# 1-Schematic_ESP-BOX-USB.net
KiCad netlist of a schematic drawn in EasyEDA
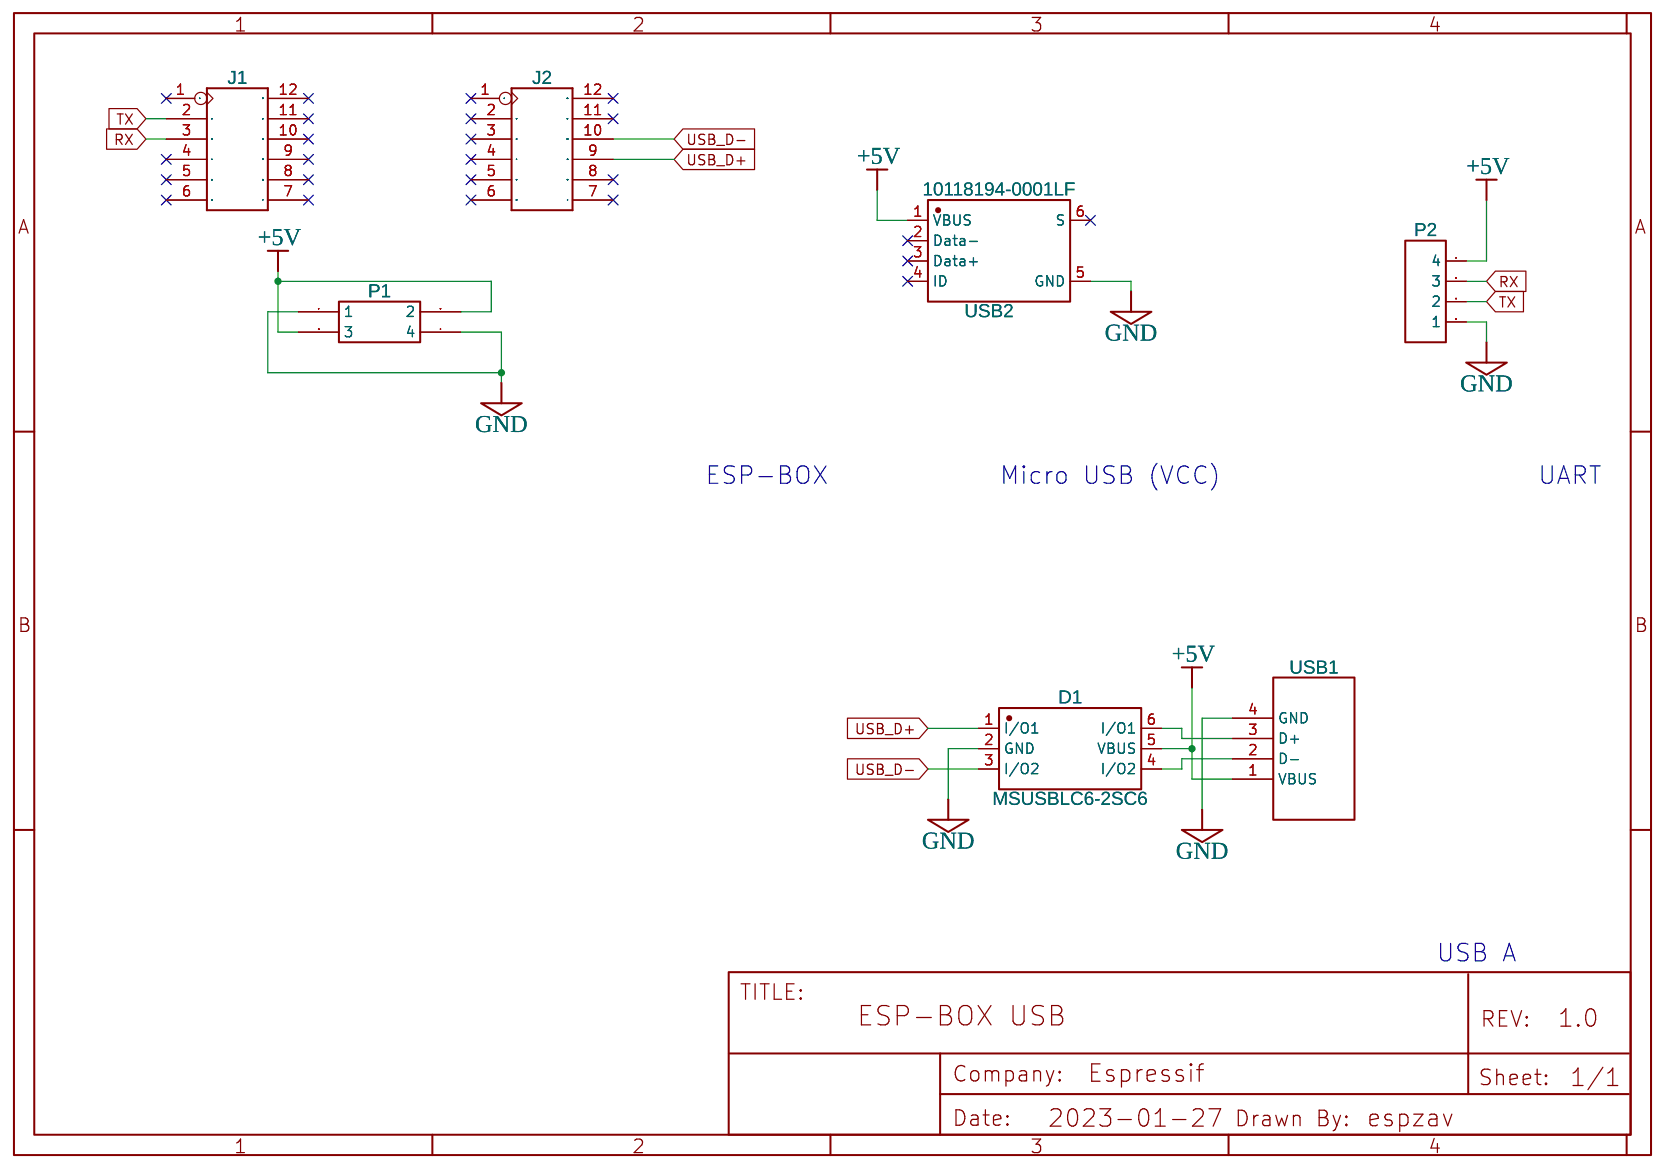
[diagram p0: schematic sheet]

(export (version "E")
  (design (tool "Eeschema 10.0.6"))
  (components
    (comp (ref "D1")
      (value "MSUSBLC6-2SC6")
      (fields (field (name "BOM_Supplier Part") "C2830148"))
      (libsource (lib "") (part "MSUSBLC6-2SC6"))
    )
    (comp (ref "J1") (value "P125-1212A0AS116A1") (libsource (lib "") (part "P125-1212A0AS116A1")))
    (comp (ref "J2") (value "P125-1212A0AS116A1") (libsource (lib "") (part "P125-1212A0AS116A1")))
    (comp (ref "P1")
      (value "Female header/2.54mm2x2 Female header")
      (fields (field (name "BOM_Supplier Part") "undefined"))
      (libsource (lib "") (part "Female header/2.54mm2x2 Female header"))
    )
    (comp (ref "P2")
      (value "Header-Female-2.54_1x4")
      (fields (field (name "BOM_Supplier Part") "C124413"))
      (libsource (lib "") (part "Header-Female-2.54_1x4"))
    )
    (comp (ref "USB1")
      (value "USB-A-S-F-B-TH-R USB Type A Connector")
      (fields
        (field (name "BOM_Manufacturer Part") "USB-A-S-F-B-TH-R")
        (field (name "BOM_Supplier Part") "SAM10861-ND")
      )
      (libsource (lib "") (part "USB-A-S-F-B-TH-R USB Type A Connector"))
    )
    (comp (ref "USB2")
      (value "10118194-0001LF")
      (fields (field (name "BOM_Supplier Part") "C132563"))
      (libsource (lib "") (part "10118194-0001LF"))
    )
  )
  (nets
    (net (code "1") (name "+5V") (class "Default")
      (node (ref "D1") (pin "5") (pinfunction "VBUS_5") (pintype "unspecified"))
      (node (ref "P1") (pin "2") (pinfunction "2_2") (pintype "input"))
      (node (ref "P1") (pin "3") (pinfunction "3_3") (pintype "input"))
      (node (ref "P2") (pin "4") (pinfunction "4_4") (pintype "input"))
      (node (ref "USB1") (pin "1") (pinfunction "VBUS_1") (pintype "unspecified"))
      (node (ref "USB2") (pin "1") (pinfunction "VBUS_1") (pintype "unspecified"))
    )
    (net (code "2") (name "GND") (class "Default")
      (node (ref "D1") (pin "2") (pinfunction "GND_2") (pintype "unspecified"))
      (node (ref "P1") (pin "1") (pinfunction "1_1") (pintype "input"))
      (node (ref "P1") (pin "4") (pinfunction "4_4") (pintype "input"))
      (node (ref "P2") (pin "1") (pinfunction "1_1") (pintype "input"))
      (node (ref "USB1") (pin "4") (pinfunction "GND_4") (pintype "unspecified"))
      (node (ref "USB2") (pin "5") (pinfunction "GND_5") (pintype "unspecified"))
    )
    (net (code "3") (name "Net-(USB1-D+)") (class "Default")
      (node (ref "D1") (pin "6") (pinfunction "I/O1_6") (pintype "unspecified"))
      (node (ref "USB1") (pin "3") (pinfunction "D+_3") (pintype "unspecified"))
    )
    (net (code "4") (name "Net-(USB1-D-)") (class "Default")
      (node (ref "D1") (pin "4") (pinfunction "I/O2_4") (pintype "unspecified"))
      (node (ref "USB1") (pin "2") (pinfunction "D-_2") (pintype "unspecified"))
    )
    (net (code "5") (name "RX") (class "Default")
      (node (ref "J1") (pin "3") (pinfunction "3_3") (pintype "unspecified"))
      (node (ref "P2") (pin "3") (pinfunction "3_3") (pintype "input"))
    )
    (net (code "6") (name "TX") (class "Default")
      (node (ref "J1") (pin "2") (pinfunction "2_2") (pintype "unspecified"))
      (node (ref "P2") (pin "2") (pinfunction "2_2") (pintype "input"))
    )
    (net (code "7") (name "USB_D+") (class "Default")
      (node (ref "D1") (pin "1") (pinfunction "I/O1_1") (pintype "unspecified"))
      (node (ref "J2") (pin "9") (pinfunction "9_9") (pintype "unspecified"))
    )
    (net (code "8") (name "USB_D-") (class "Default")
      (node (ref "D1") (pin "3") (pinfunction "I/O2_3") (pintype "unspecified"))
      (node (ref "J2") (pin "10") (pinfunction "10_10") (pintype "unspecified"))
    )
    (net (code "9") (name "unconnected-(J1-Pad1)") (class "Default")
      (node (ref "J1") (pin "1") (pinfunction "1_1") (pintype "unspecified+no_connect"))
    )
    (net (code "10") (name "unconnected-(J1-Pad4)") (class "Default")
      (node (ref "J1") (pin "4") (pinfunction "4_4") (pintype "unspecified+no_connect"))
    )
    (net (code "11") (name "unconnected-(J1-Pad5)") (class "Default")
      (node (ref "J1") (pin "5") (pinfunction "5_5") (pintype "unspecified+no_connect"))
    )
    (net (code "12") (name "unconnected-(J1-Pad6)") (class "Default")
      (node (ref "J1") (pin "6") (pinfunction "6_6") (pintype "unspecified+no_connect"))
    )
    (net (code "13") (name "unconnected-(J1-Pad7)") (class "Default")
      (node (ref "J1") (pin "7") (pinfunction "7_7") (pintype "unspecified+no_connect"))
    )
    (net (code "14") (name "unconnected-(J1-Pad8)") (class "Default")
      (node (ref "J1") (pin "8") (pinfunction "8_8") (pintype "unspecified+no_connect"))
    )
    (net (code "15") (name "unconnected-(J1-Pad9)") (class "Default")
      (node (ref "J1") (pin "9") (pinfunction "9_9") (pintype "unspecified+no_connect"))
    )
    (net (code "16") (name "unconnected-(J1-Pad10)") (class "Default")
      (node (ref "J1") (pin "10") (pinfunction "10_10") (pintype "unspecified+no_connect"))
    )
    (net (code "17") (name "unconnected-(J1-Pad11)") (class "Default")
      (node (ref "J1") (pin "11") (pinfunction "11_11") (pintype "unspecified+no_connect"))
    )
    (net (code "18") (name "unconnected-(J1-Pad12)") (class "Default")
      (node (ref "J1") (pin "12") (pinfunction "12_12") (pintype "unspecified+no_connect"))
    )
    (net (code "19") (name "unconnected-(J2-Pad1)") (class "Default")
      (node (ref "J2") (pin "1") (pinfunction "1_1") (pintype "unspecified+no_connect"))
    )
    (net (code "20") (name "unconnected-(J2-Pad2)") (class "Default")
      (node (ref "J2") (pin "2") (pinfunction "2_2") (pintype "unspecified+no_connect"))
    )
    (net (code "21") (name "unconnected-(J2-Pad3)") (class "Default")
      (node (ref "J2") (pin "3") (pinfunction "3_3") (pintype "unspecified+no_connect"))
    )
    (net (code "22") (name "unconnected-(J2-Pad4)") (class "Default")
      (node (ref "J2") (pin "4") (pinfunction "4_4") (pintype "unspecified+no_connect"))
    )
    (net (code "23") (name "unconnected-(J2-Pad5)") (class "Default")
      (node (ref "J2") (pin "5") (pinfunction "5_5") (pintype "unspecified+no_connect"))
    )
    (net (code "24") (name "unconnected-(J2-Pad6)") (class "Default")
      (node (ref "J2") (pin "6") (pinfunction "6_6") (pintype "unspecified+no_connect"))
    )
    (net (code "25") (name "unconnected-(J2-Pad7)") (class "Default")
      (node (ref "J2") (pin "7") (pinfunction "7_7") (pintype "unspecified+no_connect"))
    )
    (net (code "26") (name "unconnected-(J2-Pad8)") (class "Default")
      (node (ref "J2") (pin "8") (pinfunction "8_8") (pintype "unspecified+no_connect"))
    )
    (net (code "27") (name "unconnected-(J2-Pad11)") (class "Default")
      (node (ref "J2") (pin "11") (pinfunction "11_11") (pintype "unspecified+no_connect"))
    )
    (net (code "28") (name "unconnected-(J2-Pad12)") (class "Default")
      (node (ref "J2") (pin "12") (pinfunction "12_12") (pintype "unspecified+no_connect"))
    )
    (net (code "29") (name "unconnected-(USB2-Data+-Pad3)") (class "Default")
      (node (ref "USB2") (pin "3") (pinfunction "Data+_3") (pintype "unspecified+no_connect"))
    )
    (net (code "30") (name "unconnected-(USB2-Data--Pad2)") (class "Default")
      (node (ref "USB2") (pin "2") (pinfunction "Data-_2") (pintype "unspecified+no_connect"))
    )
    (net (code "31") (name "unconnected-(USB2-ID-Pad4)") (class "Default")
      (node (ref "USB2") (pin "4") (pinfunction "ID_4") (pintype "unspecified+no_connect"))
    )
    (net (code "32") (name "unconnected-(USB2-S-Pad6)") (class "Default")
      (node (ref "USB2") (pin "6") (pinfunction "S_6") (pintype "unspecified+no_connect"))
    )
  )
)
